# SCH_Pendant_YSWS_2026-06-23.net
KiCad netlist of a schematic drawn in EasyEDA
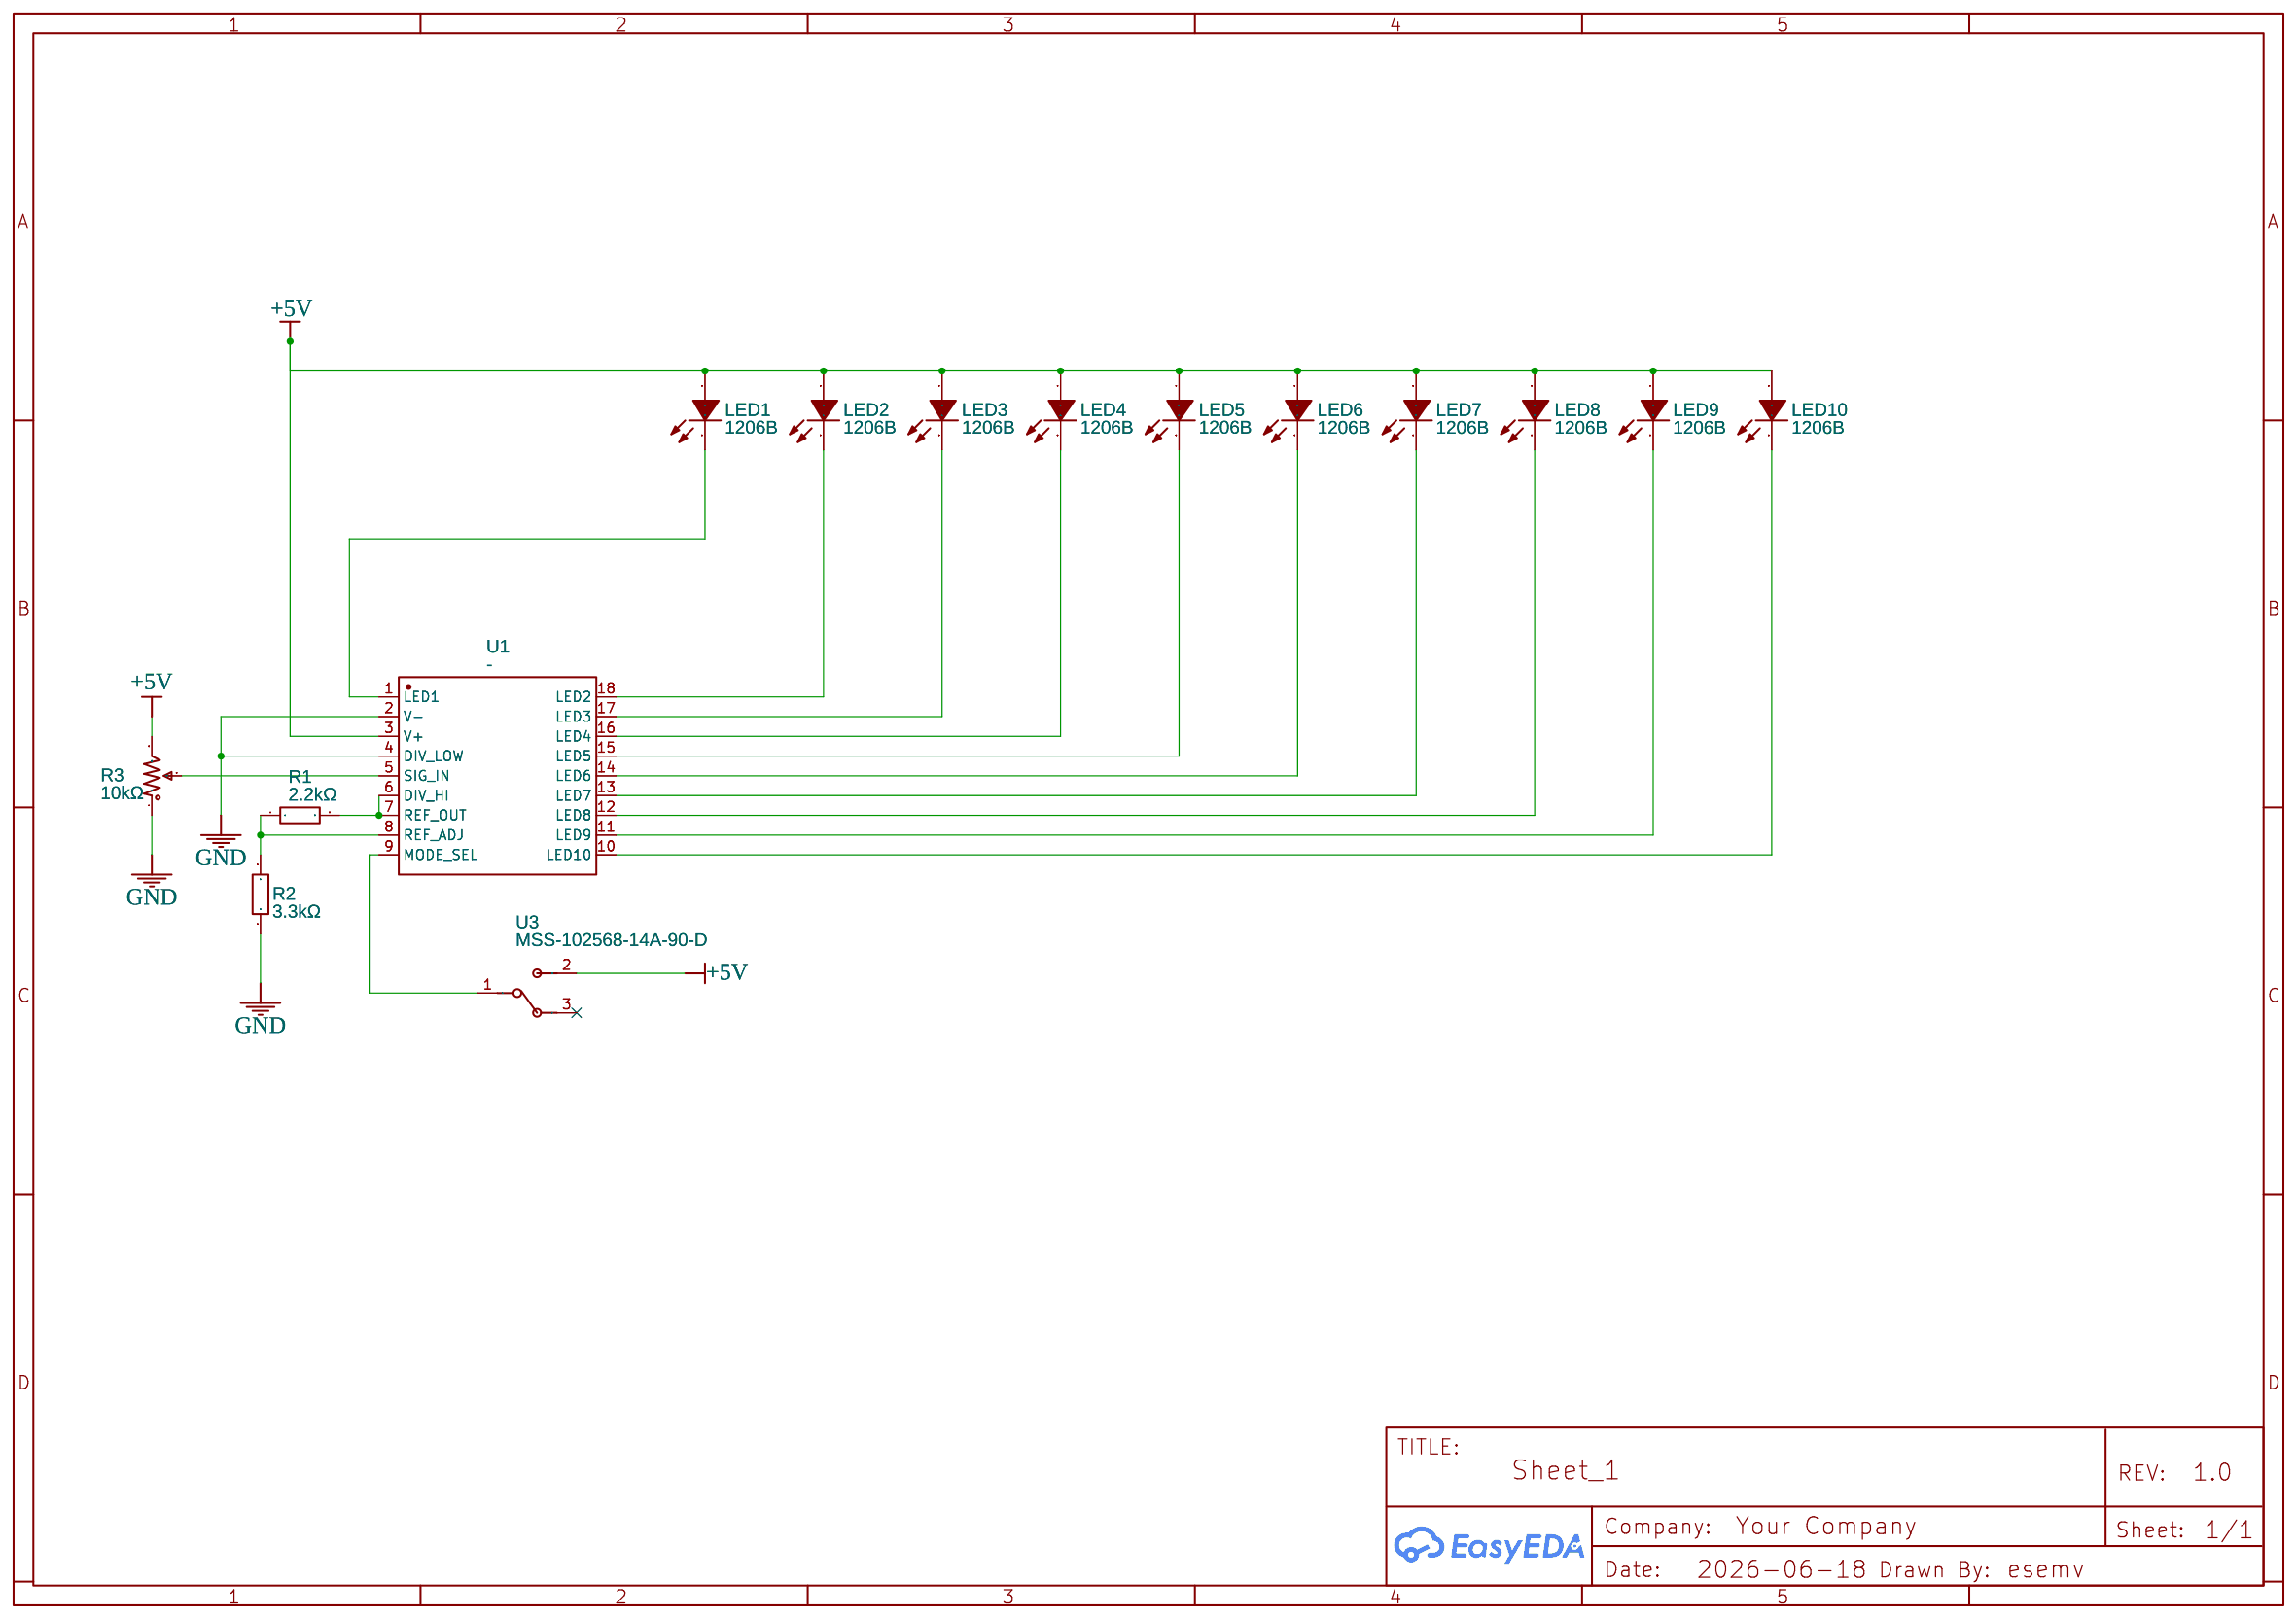
[diagram p0: schematic sheet]

(export (version "E")
  (design (tool "Eeschema 10.0.6"))
  (components
    (comp (ref "LED1")
      (value "1206B")
      (fields (field (name "Manufacturer Part") "KT-1206B") (field (name "Manufacturer") "KENTO"))
      (libsource (lib "") (part "1206B"))
    )
    (comp (ref "LED2")
      (value "1206B")
      (fields (field (name "Manufacturer Part") "KT-1206B") (field (name "Manufacturer") "KENTO"))
      (libsource (lib "") (part "1206B"))
    )
    (comp (ref "LED3")
      (value "1206B")
      (fields (field (name "Manufacturer Part") "KT-1206B") (field (name "Manufacturer") "KENTO"))
      (libsource (lib "") (part "1206B"))
    )
    (comp (ref "LED4")
      (value "1206B")
      (fields (field (name "Manufacturer Part") "KT-1206B") (field (name "Manufacturer") "KENTO"))
      (libsource (lib "") (part "1206B"))
    )
    (comp (ref "LED5")
      (value "1206B")
      (fields (field (name "Manufacturer Part") "KT-1206B") (field (name "Manufacturer") "KENTO"))
      (libsource (lib "") (part "1206B"))
    )
    (comp (ref "LED6")
      (value "1206B")
      (fields (field (name "Manufacturer Part") "KT-1206B") (field (name "Manufacturer") "KENTO"))
      (libsource (lib "") (part "1206B"))
    )
    (comp (ref "LED7")
      (value "1206B")
      (fields (field (name "Manufacturer Part") "KT-1206B") (field (name "Manufacturer") "KENTO"))
      (libsource (lib "") (part "1206B"))
    )
    (comp (ref "LED8")
      (value "1206B")
      (fields (field (name "Manufacturer Part") "KT-1206B") (field (name "Manufacturer") "KENTO"))
      (libsource (lib "") (part "1206B"))
    )
    (comp (ref "LED9")
      (value "1206B")
      (fields (field (name "Manufacturer Part") "KT-1206B") (field (name "Manufacturer") "KENTO"))
      (libsource (lib "") (part "1206B"))
    )
    (comp (ref "LED10")
      (value "1206B")
      (fields (field (name "Manufacturer Part") "KT-1206B") (field (name "Manufacturer") "KENTO"))
      (libsource (lib "") (part "1206B"))
    )
    (comp (ref "R1")
      (value "2.2kΩ")
      (fields
        (field (name "Manufacturer Part") "MF1/8W-2.2KΩ±1% T")
        (field (name "Manufacturer") "CCO(千志电子)")
      )
      (libsource (lib "") (part "MF1/8W-2.2KΩ±1% T52"))
    )
    (comp (ref "R2")
      (value "3.3kΩ")
      (fields
        (field (name "Manufacturer Part") "MF1/4W-3.3KΩ±1% T")
        (field (name "Manufacturer") "CCO(千志电子)")
      )
      (libsource (lib "") (part "MF1/4W-3.3KΩ±1% T52"))
    )
    (comp (ref "R3")
      (value "10kΩ")
      (fields (field (name "Manufacturer Part") "3386P-1-103TLF") (field (name "Manufacturer") "BOURNS"))
      (libsource (lib "") (part "3386P-1-103TLF"))
    )
    (comp (ref "U1")
      (value "-")
      (fields (field (name "Manufacturer Part") "LM3914"))
      (libsource (lib "") (part "LM3914"))
    )
    (comp (ref "U3")
      (value "MSS-102568-14A-90-D")
      (fields (field (name "Manufacturer") "CUI"))
      (libsource (lib "") (part "MSS-102568-14A-90-D"))
    )
  )
  (nets
    (net (code "1") (name "+5V") (class "Default")
      (node (ref "LED1") (pin "1") (pinfunction "1_1") (pintype "unspecified"))
      (node (ref "LED10") (pin "1") (pinfunction "1_1") (pintype "unspecified"))
      (node (ref "LED2") (pin "1") (pinfunction "1_1") (pintype "unspecified"))
      (node (ref "LED3") (pin "1") (pinfunction "1_1") (pintype "unspecified"))
      (node (ref "LED4") (pin "1") (pinfunction "1_1") (pintype "unspecified"))
      (node (ref "LED5") (pin "1") (pinfunction "1_1") (pintype "unspecified"))
      (node (ref "LED6") (pin "1") (pinfunction "1_1") (pintype "unspecified"))
      (node (ref "LED7") (pin "1") (pinfunction "1_1") (pintype "unspecified"))
      (node (ref "LED8") (pin "1") (pinfunction "1_1") (pintype "unspecified"))
      (node (ref "LED9") (pin "1") (pinfunction "1_1") (pintype "unspecified"))
      (node (ref "R3") (pin "3") (pinfunction "3_3") (pintype "unspecified"))
      (node (ref "U1") (pin "3") (pinfunction "V+_3") (pintype "unspecified"))
      (node (ref "U3") (pin "2") (pinfunction "2_2") (pintype "unspecified"))
    )
    (net (code "2") (name "GND") (class "Default")
      (node (ref "R2") (pin "1") (pinfunction "1_1") (pintype "unspecified"))
      (node (ref "R3") (pin "1") (pinfunction "1_1") (pintype "unspecified"))
      (node (ref "U1") (pin "2") (pinfunction "V-_2") (pintype "unspecified"))
      (node (ref "U1") (pin "4") (pinfunction "DIV_LOW_4") (pintype "unspecified"))
    )
    (net (code "3") (name "Net-(U1-DIV_HI)") (class "Default")
      (node (ref "R1") (pin "2") (pinfunction "2_2") (pintype "unspecified"))
      (node (ref "U1") (pin "6") (pinfunction "DIV_HI_6") (pintype "unspecified"))
      (node (ref "U1") (pin "7") (pinfunction "REF_OUT_7") (pintype "unspecified"))
    )
    (net (code "4") (name "Net-(U1-LED1)") (class "Default")
      (node (ref "LED1") (pin "2") (pinfunction "2_2") (pintype "unspecified"))
      (node (ref "U1") (pin "1") (pinfunction "LED1_1") (pintype "unspecified"))
    )
    (net (code "5") (name "Net-(U1-LED2)") (class "Default")
      (node (ref "LED2") (pin "2") (pinfunction "2_2") (pintype "unspecified"))
      (node (ref "U1") (pin "18") (pinfunction "LED2_18") (pintype "unspecified"))
    )
    (net (code "6") (name "Net-(U1-LED3)") (class "Default")
      (node (ref "LED3") (pin "2") (pinfunction "2_2") (pintype "unspecified"))
      (node (ref "U1") (pin "17") (pinfunction "LED3_17") (pintype "unspecified"))
    )
    (net (code "7") (name "Net-(U1-LED4)") (class "Default")
      (node (ref "LED4") (pin "2") (pinfunction "2_2") (pintype "unspecified"))
      (node (ref "U1") (pin "16") (pinfunction "LED4_16") (pintype "unspecified"))
    )
    (net (code "8") (name "Net-(U1-LED5)") (class "Default")
      (node (ref "LED5") (pin "2") (pinfunction "2_2") (pintype "unspecified"))
      (node (ref "U1") (pin "15") (pinfunction "LED5_15") (pintype "unspecified"))
    )
    (net (code "9") (name "Net-(U1-LED6)") (class "Default")
      (node (ref "LED6") (pin "2") (pinfunction "2_2") (pintype "unspecified"))
      (node (ref "U1") (pin "14") (pinfunction "LED6_14") (pintype "unspecified"))
    )
    (net (code "10") (name "Net-(U1-LED7)") (class "Default")
      (node (ref "LED7") (pin "2") (pinfunction "2_2") (pintype "unspecified"))
      (node (ref "U1") (pin "13") (pinfunction "LED7_13") (pintype "unspecified"))
    )
    (net (code "11") (name "Net-(U1-LED8)") (class "Default")
      (node (ref "LED8") (pin "2") (pinfunction "2_2") (pintype "unspecified"))
      (node (ref "U1") (pin "12") (pinfunction "LED8_12") (pintype "unspecified"))
    )
    (net (code "12") (name "Net-(U1-LED9)") (class "Default")
      (node (ref "LED9") (pin "2") (pinfunction "2_2") (pintype "unspecified"))
      (node (ref "U1") (pin "11") (pinfunction "LED9_11") (pintype "unspecified"))
    )
    (net (code "13") (name "Net-(U1-LED10)") (class "Default")
      (node (ref "LED10") (pin "2") (pinfunction "2_2") (pintype "unspecified"))
      (node (ref "U1") (pin "10") (pinfunction "LED10_10") (pintype "unspecified"))
    )
    (net (code "14") (name "Net-(U1-MODE_SEL)") (class "Default")
      (node (ref "U1") (pin "9") (pinfunction "MODE_SEL_9") (pintype "unspecified"))
      (node (ref "U3") (pin "1") (pinfunction "1_1") (pintype "unspecified"))
    )
    (net (code "15") (name "Net-(U1-REF_ADJ)") (class "Default")
      (node (ref "R1") (pin "1") (pinfunction "1_1") (pintype "unspecified"))
      (node (ref "R2") (pin "2") (pinfunction "2_2") (pintype "unspecified"))
      (node (ref "U1") (pin "8") (pinfunction "REF_ADJ_8") (pintype "unspecified"))
    )
    (net (code "16") (name "Net-(U1-SIG_IN)") (class "Default")
      (node (ref "R3") (pin "2") (pinfunction "2_2") (pintype "unspecified"))
      (node (ref "U1") (pin "5") (pinfunction "SIG_IN_5") (pintype "unspecified"))
    )
    (net (code "17") (name "unconnected-(U3-Pad3)") (class "Default")
      (node (ref "U3") (pin "3") (pinfunction "3_3") (pintype "unspecified+no_connect"))
    )
  )
)
